# ISO_Power.net
KiCad netlist of a schematic drawn in Altium Designer
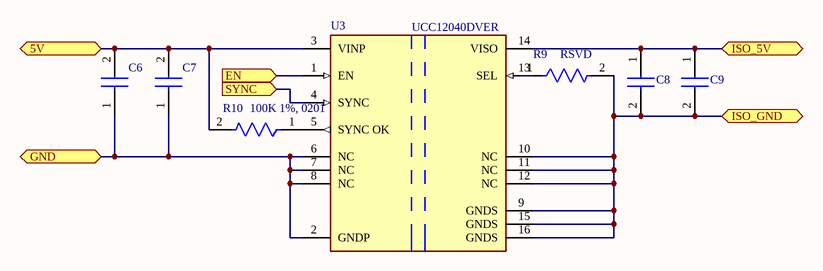
[diagram p0: ISO_Power.SchDoc]

(export (version "E")
  (design (tool "Eeschema 10.0.6"))
  (components
    (comp (ref "C6")
      (value "10 uF, 25V, X6S, 0402")
      (footprint "SamacSys:CAPC1005X70N")
      (description "Capacitor")
      (fields
        (field (name "MANUFACTURER_PART_NUMBER") "GRM155F51E104ZA01E")
        (field (name "MOUSER PART NUMBER") "81-GRM15F51E104ZA01E")
      )
      (libsource (lib "*") (part "GRM155F51E104ZA01E"))
    )
    (comp (ref "C7")
      (value "100 nF, 25V, X6S, 0201")
      (footprint "SamacSys:CAPC0603X33N")
      (description "Capacitor")
      (fields
        (field (name "MANUFACTURER_PART_NUMBER") "GRM033C81E104KE14D")
        (field (name "MOUSER PART NUMBER") "81-GRM33C81E104KE14D")
      )
      (libsource (lib "*") (part "GRM033C81E104KE14D"))
    )
    (comp (ref "C8")
      (value "100 nF, 25V, X6S, 0201")
      (footprint "SamacSys:CAPC0603X33N")
      (description "Capacitor")
      (fields
        (field (name "MANUFACTURER_PART_NUMBER") "GRM033C81E104KE14D")
        (field (name "MOUSER PART NUMBER") "81-GRM33C81E104KE14D")
      )
      (libsource (lib "*") (part "GRM033C81E104KE14D"))
    )
    (comp (ref "C9")
      (value "10 uF, 25V, X6S, 0402")
      (footprint "SamacSys:CAPC1005X70N")
      (description "Capacitor")
      (fields
        (field (name "MANUFACTURER_PART_NUMBER") "GRM155F51E104ZA01E")
        (field (name "MOUSER PART NUMBER") "81-GRM15F51E104ZA01E")
      )
      (libsource (lib "*") (part "GRM155F51E104ZA01E"))
    )
    (comp (ref "R9")
      (value "RSVD")
      (footprint "FP-ERJ1GN-IPC_A")
      (description "RES SMD 100K OHM 1% 1/20W 0201")
      (fields (field (name "TOLERANCE") "1%"))
      (libsource (lib "Altium Content Vault") (part "1029c3af85768c4190bb7ad29bc67b5"))
    )
    (comp (ref "R10")
      (value "100K 1%, 0201")
      (footprint "FP-ERJ1GN-IPC_A")
      (description "RES SMD 100K OHM 1% 1/20W 0201")
      (fields (field (name "TOLERANCE") "1%"))
      (libsource (lib "Altium Content Vault") (part "1029c3af85768c4190bb7ad29bc67b5"))
    )
    (comp (ref "U3")
      (value "UCC12040DVER")
      (footprint "FP-DVE0016A-MFG")
      (description "DC DC CONVERTER 3.3V 5V 500MW")
      (libsource (lib "Altium Content Vault") (part "cf9dcfd4a8b3775ff5e4cba6f3e7206"))
    )
  )
  (nets
    (net (code "1") (name "/5V") (class "Default")
      (node (ref "C6") (pin "2") (pinfunction "2_2") (pintype "passive"))
      (node (ref "C7") (pin "2") (pinfunction "2_2") (pintype "passive"))
      (node (ref "R10") (pin "2") (pinfunction "2_2") (pintype "passive"))
      (node (ref "U3") (pin "3") (pinfunction "VINP_3") (pintype "power_in"))
    )
    (net (code "2") (name "/EN") (class "Default")
      (node (ref "U3") (pin "1") (pinfunction "EN_1") (pintype "input"))
    )
    (net (code "3") (name "/GND") (class "Default")
      (node (ref "C6") (pin "1") (pinfunction "1_1") (pintype "passive"))
      (node (ref "C7") (pin "1") (pinfunction "1_1") (pintype "passive"))
      (node (ref "U3") (pin "2") (pinfunction "GNDP_2") (pintype "power_in"))
      (node (ref "U3") (pin "6") (pinfunction "NC_6") (pintype "passive"))
      (node (ref "U3") (pin "7") (pinfunction "NC_7") (pintype "passive"))
      (node (ref "U3") (pin "8") (pinfunction "NC_8") (pintype "passive"))
    )
    (net (code "4") (name "/ISO_5V") (class "Default")
      (node (ref "C8") (pin "1") (pinfunction "1_1") (pintype "passive"))
      (node (ref "C9") (pin "1") (pinfunction "1_1") (pintype "passive"))
      (node (ref "U3") (pin "14") (pinfunction "VISO_14") (pintype "power_in"))
    )
    (net (code "5") (name "/ISO_GND") (class "Default")
      (node (ref "C8") (pin "2") (pinfunction "2_2") (pintype "passive"))
      (node (ref "C9") (pin "2") (pinfunction "2_2") (pintype "passive"))
      (node (ref "R9") (pin "2") (pinfunction "2_2") (pintype "passive"))
      (node (ref "U3") (pin "10") (pinfunction "NC_10") (pintype "passive"))
      (node (ref "U3") (pin "11") (pinfunction "NC_11") (pintype "passive"))
      (node (ref "U3") (pin "12") (pinfunction "NC_12") (pintype "passive"))
      (node (ref "U3") (pin "15") (pinfunction "GNDS_15") (pintype "power_in"))
      (node (ref "U3") (pin "16") (pinfunction "GNDS_16") (pintype "power_in"))
      (node (ref "U3") (pin "9") (pinfunction "GNDS_9") (pintype "power_in"))
    )
    (net (code "6") (name "/SYNC") (class "Default")
      (node (ref "U3") (pin "4") (pinfunction "SYNC_4") (pintype "input"))
    )
    (net (code "7") (name "Net-(U3-SEL)") (class "Default")
      (node (ref "R9") (pin "1") (pinfunction "1_1") (pintype "passive"))
      (node (ref "U3") (pin "13") (pinfunction "SEL_13") (pintype "input"))
    )
    (net (code "8") (name "Net-(U3-SYNC_OK)") (class "Default")
      (node (ref "R10") (pin "1") (pinfunction "1_1") (pintype "passive"))
      (node (ref "U3") (pin "5") (pinfunction "SYNC_OK_5") (pintype "output"))
    )
  )
)
